# Quarantatre.net
KiCad netlist of a schematic drawn in EAGLE
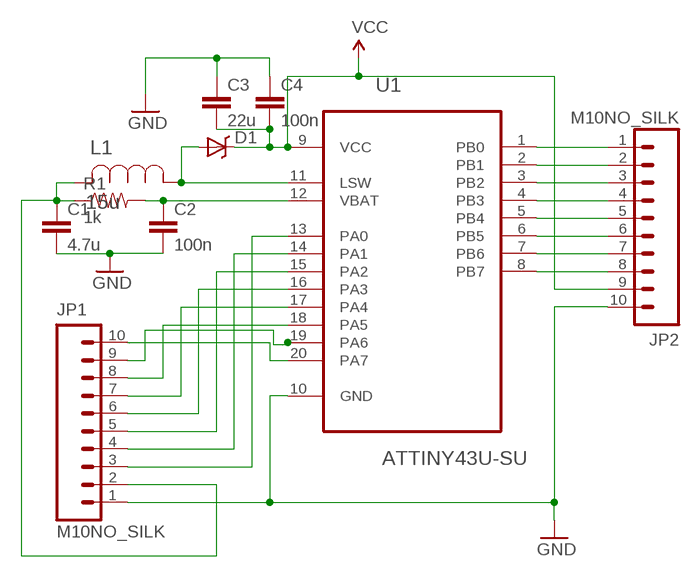
[diagram p0: schematic, sheet 1]

(export (version "E")
  (design (tool "Eeschema 10.0.6"))
  (components
    (comp (ref "C1")
      (value "4.7u")
      (footprint "eagle-import:C0805")
      (libsource (lib "eagle-import") (part "C-EUC0805"))
    )
    (comp (ref "C2")
      (value "100n")
      (footprint "eagle-import:0603-CAP")
      (libsource (lib "eagle-import") (part "CAP0603-CAP"))
    )
    (comp (ref "C3")
      (value "22u")
      (footprint "eagle-import:C0805")
      (libsource (lib "eagle-import") (part "C-EUC0805"))
    )
    (comp (ref "C4")
      (value "100n")
      (footprint "eagle-import:0603-CAP")
      (libsource (lib "eagle-import") (part "CAP0603-CAP"))
    )
    (comp (ref "D1")
      (value "BAT20JFILM")
      (footprint "eagle-import:SOD-323")
      (libsource (lib "eagle-import") (part "BAT20JFILM"))
    )
    (comp (ref "JP1")
      (value "M10NO_SILK")
      (footprint "eagle-import:1X10_NO_SILK")
      (libsource (lib "eagle-import") (part "M10NO_SILK"))
    )
    (comp (ref "JP2")
      (value "M10NO_SILK")
      (footprint "eagle-import:1X10_NO_SILK")
      (libsource (lib "eagle-import") (part "M10NO_SILK"))
    )
    (comp (ref "L1")
      (value "15u")
      (footprint "eagle-import:IND4040")
      (libsource (lib "eagle-import") (part "NRS4012T150MDGJ"))
    )
    (comp (ref "R1")
      (value "1k")
      (footprint "eagle-import:0603-RES")
      (libsource (lib "eagle-import") (part "RESISTOR0603-RES"))
    )
    (comp (ref "U1")
      (value "ATTINY43U-SU")
      (footprint "eagle-import:SOIC127P1032X265-20N")
      (libsource (lib "eagle-import") (part "ATTINY43U-SU"))
    )
  )
  (nets
    (net (code "1") (name "GND") (class "Default")
      (node (ref "C1") (pin "2") (pinfunction "2_2") (pintype "passive"))
      (node (ref "C2") (pin "2") (pinfunction "2_2") (pintype "passive"))
      (node (ref "C3") (pin "1") (pinfunction "1_1") (pintype "passive"))
      (node (ref "C4") (pin "1") (pinfunction "1_1") (pintype "passive"))
      (node (ref "JP1") (pin "1") (pinfunction "1_1") (pintype "passive"))
      (node (ref "JP2") (pin "10") (pinfunction "10_10") (pintype "passive"))
      (node (ref "U1") (pin "10") (pinfunction "GND_10") (pintype "passive"))
    )
    (net (code "2") (name "Net-(D1-A)") (class "Default")
      (node (ref "D1") (pin "2") (pinfunction "A_2") (pintype "passive"))
      (node (ref "L1") (pin "P$1") (pinfunction "1_P$1") (pintype "passive"))
      (node (ref "U1") (pin "11") (pinfunction "LSW_11") (pintype "passive"))
    )
    (net (code "3") (name "Net-(L1-2)") (class "Default")
      (node (ref "C1") (pin "1") (pinfunction "1_1") (pintype "passive"))
      (node (ref "JP1") (pin "2") (pinfunction "2_2") (pintype "passive"))
      (node (ref "L1") (pin "P$2") (pinfunction "2_P$2") (pintype "passive"))
      (node (ref "R1") (pin "1") (pinfunction "1_1") (pintype "passive"))
    )
    (net (code "4") (name "Net-(U1-PA0)") (class "Default")
      (node (ref "JP1") (pin "3") (pinfunction "3_3") (pintype "passive"))
      (node (ref "U1") (pin "13") (pinfunction "PA0_13") (pintype "bidirectional"))
    )
    (net (code "5") (name "Net-(U1-PA1)") (class "Default")
      (node (ref "JP1") (pin "4") (pinfunction "4_4") (pintype "passive"))
      (node (ref "U1") (pin "14") (pinfunction "PA1_14") (pintype "bidirectional"))
    )
    (net (code "6") (name "Net-(U1-PA2)") (class "Default")
      (node (ref "JP1") (pin "5") (pinfunction "5_5") (pintype "passive"))
      (node (ref "U1") (pin "15") (pinfunction "PA2_15") (pintype "bidirectional"))
    )
    (net (code "7") (name "Net-(U1-PA3)") (class "Default")
      (node (ref "JP1") (pin "6") (pinfunction "6_6") (pintype "passive"))
      (node (ref "U1") (pin "16") (pinfunction "PA3_16") (pintype "bidirectional"))
    )
    (net (code "8") (name "Net-(U1-PA4)") (class "Default")
      (node (ref "JP1") (pin "7") (pinfunction "7_7") (pintype "passive"))
      (node (ref "U1") (pin "17") (pinfunction "PA4_17") (pintype "bidirectional"))
    )
    (net (code "9") (name "Net-(U1-PA5)") (class "Default")
      (node (ref "JP1") (pin "8") (pinfunction "8_8") (pintype "passive"))
      (node (ref "U1") (pin "18") (pinfunction "PA5_18") (pintype "bidirectional"))
    )
    (net (code "10") (name "Net-(U1-PA6)") (class "Default")
      (node (ref "JP1") (pin "9") (pinfunction "9_9") (pintype "passive"))
      (node (ref "U1") (pin "19") (pinfunction "PA6_19") (pintype "bidirectional"))
    )
    (net (code "11") (name "Net-(U1-PA7)") (class "Default")
      (node (ref "JP1") (pin "10") (pinfunction "10_10") (pintype "passive"))
      (node (ref "U1") (pin "20") (pinfunction "PA7_20") (pintype "bidirectional"))
    )
    (net (code "12") (name "Net-(U1-PB0)") (class "Default")
      (node (ref "JP2") (pin "1") (pinfunction "1_1") (pintype "passive"))
      (node (ref "U1") (pin "1") (pinfunction "PB0_1") (pintype "bidirectional"))
    )
    (net (code "13") (name "Net-(U1-PB1)") (class "Default")
      (node (ref "JP2") (pin "2") (pinfunction "2_2") (pintype "passive"))
      (node (ref "U1") (pin "2") (pinfunction "PB1_2") (pintype "bidirectional"))
    )
    (net (code "14") (name "Net-(U1-PB2)") (class "Default")
      (node (ref "JP2") (pin "3") (pinfunction "3_3") (pintype "passive"))
      (node (ref "U1") (pin "3") (pinfunction "PB2_3") (pintype "bidirectional"))
    )
    (net (code "15") (name "Net-(U1-PB3)") (class "Default")
      (node (ref "JP2") (pin "4") (pinfunction "4_4") (pintype "passive"))
      (node (ref "U1") (pin "4") (pinfunction "PB3_4") (pintype "bidirectional"))
    )
    (net (code "16") (name "Net-(U1-PB4)") (class "Default")
      (node (ref "JP2") (pin "5") (pinfunction "5_5") (pintype "passive"))
      (node (ref "U1") (pin "5") (pinfunction "PB4_5") (pintype "bidirectional"))
    )
    (net (code "17") (name "Net-(U1-PB5)") (class "Default")
      (node (ref "JP2") (pin "6") (pinfunction "6_6") (pintype "passive"))
      (node (ref "U1") (pin "6") (pinfunction "PB5_6") (pintype "bidirectional"))
    )
    (net (code "18") (name "Net-(U1-PB6)") (class "Default")
      (node (ref "JP2") (pin "7") (pinfunction "7_7") (pintype "passive"))
      (node (ref "U1") (pin "7") (pinfunction "PB6_7") (pintype "bidirectional"))
    )
    (net (code "19") (name "Net-(U1-PB7)") (class "Default")
      (node (ref "JP2") (pin "8") (pinfunction "8_8") (pintype "passive"))
      (node (ref "U1") (pin "8") (pinfunction "PB7_8") (pintype "bidirectional"))
    )
    (net (code "20") (name "Net-(U1-VBAT)") (class "Default")
      (node (ref "C2") (pin "1") (pinfunction "1_1") (pintype "passive"))
      (node (ref "R1") (pin "2") (pinfunction "2_2") (pintype "passive"))
      (node (ref "U1") (pin "12") (pinfunction "VBAT_12") (pintype "passive"))
    )
    (net (code "21") (name "VCC") (class "Default")
      (node (ref "C3") (pin "2") (pinfunction "2_2") (pintype "passive"))
      (node (ref "C4") (pin "2") (pinfunction "2_2") (pintype "passive"))
      (node (ref "D1") (pin "1") (pinfunction "C_1") (pintype "passive"))
      (node (ref "JP2") (pin "9") (pinfunction "9_9") (pintype "passive"))
      (node (ref "U1") (pin "9") (pinfunction "VCC_9") (pintype "power_in"))
    )
  )
)
